# Sheet1.net
KiCad netlist of a schematic drawn in Altium Designer
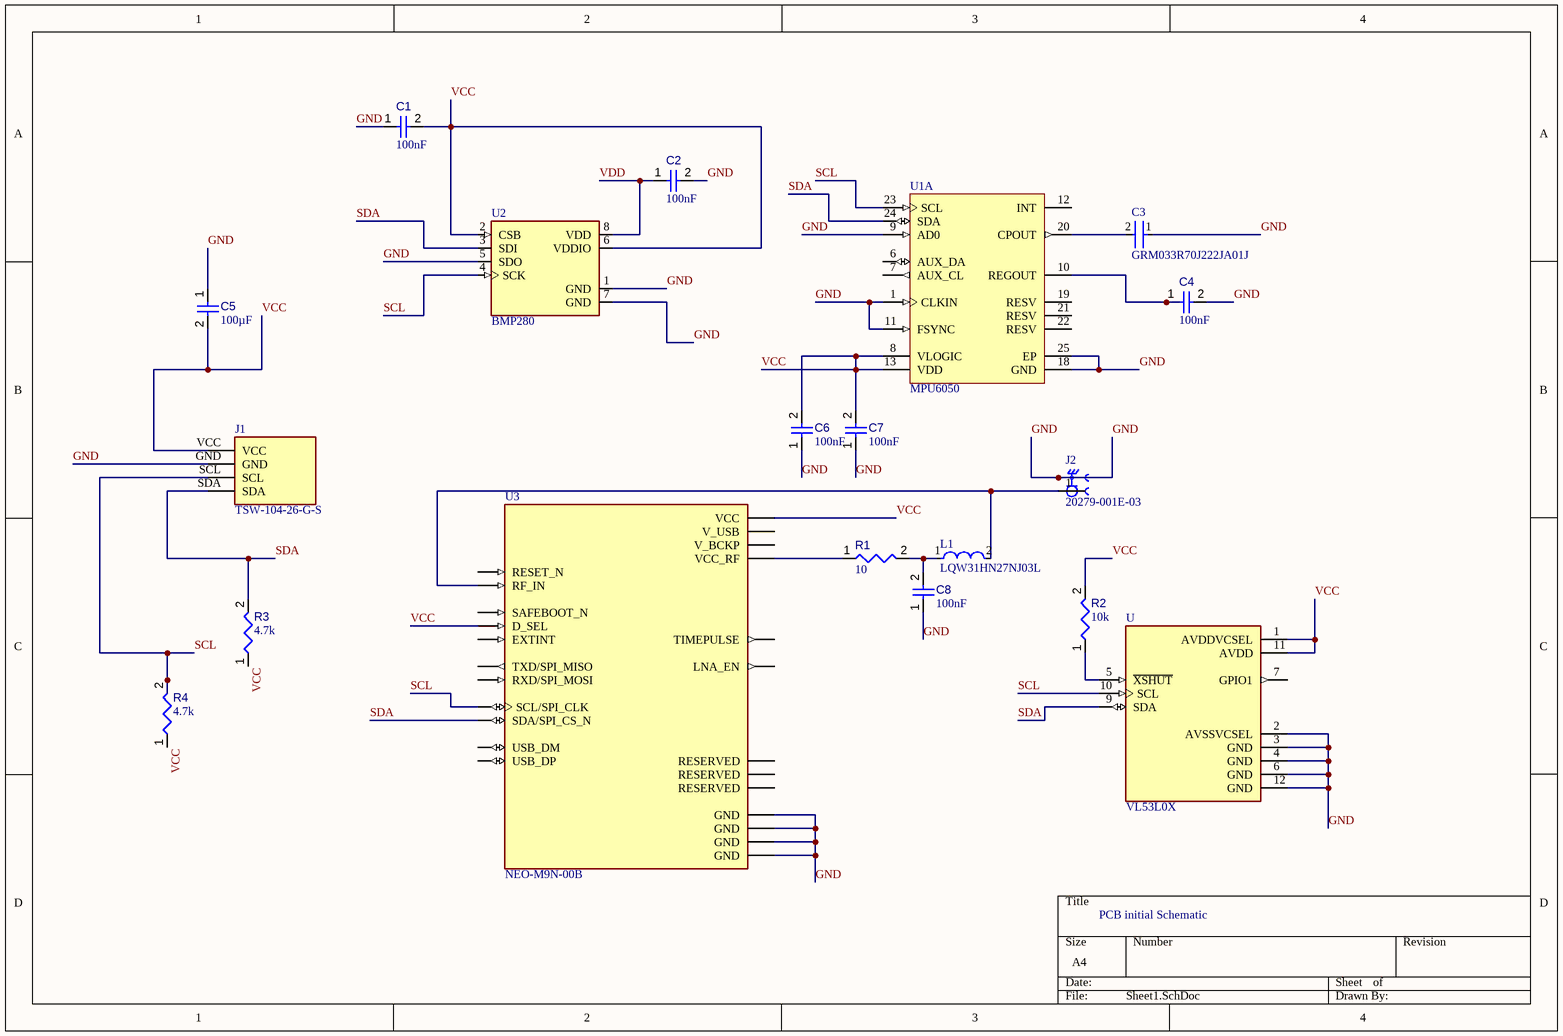
[diagram p0: Sheet1.SchDoc]

(export (version "E")
  (design (tool "Eeschema 10.0.6"))
  (components
    (comp (ref "C1")
      (value "100nF")
      (footprint "CAPC0402(1005)60_L")
      (description "Chip Capacitor, 100nF +/-20%, 10V, 0402, Thickness 0.6 mm")
      (fields (field (name "TOLERANCE") "20%") (field (name "Comment") "Capacitor 100nF +/-20% 10V 0402"))
      (libsource (lib "Lachlan Biersteker") (part "CAP-NP-2"))
    )
    (comp (ref "C2")
      (value "100nF")
      (footprint "CAPC0402(1005)60_L")
      (description "Chip Capacitor, 100nF +/-20%, 10V, 0402, Thickness 0.6 mm")
      (fields (field (name "TOLERANCE") "20%") (field (name "Comment") "Capacitor 100nF +/-20% 10V 0402"))
      (libsource (lib "Lachlan Biersteker") (part "CAP-NP-2"))
    )
    (comp (ref "C3")
      (value "GRM033R70J222JA01J")
      (footprint "FP-GRM033-0_03-IPC_B")
      (description "Chip Multilayer Ceramic Capacitors for General Purpose, 0201, 2200pF, X7R, 15%, 5%, 6.3V")
      (fields (field (name "TOLERANCE") "5%"))
      (libsource (lib "Altium Content Vault") (part "b4654b650e69147ec39a6b967a45e02"))
    )
    (comp (ref "C4")
      (value "100nF")
      (footprint "CAPC1005X56X25LL10T15")
      (description "Chip Capacitor, 0.1 uF, +/- 5%, 16 V, 0402 (1005 Metric)")
      (fields (field (name "TOLERANCE") "5%") (field (name "Comment") "Capacitor 0.1 uF +/- 5% 16 V 0402"))
      (libsource (lib "Lachlan Biersteker") (part "CAP-NP-2"))
    )
    (comp (ref "C5")
      (value "100µF")
      (footprint "CAPC0805(2012)145_L")
      (description "Chip Capacitor, 100µF +/-20%, 6.3V, 0805, Thickness 1.45 mm")
      (fields (field (name "TOLERANCE") "10%") (field (name "Comment") "Capacitor 100µF +/-20% 6.3V 0805"))
      (libsource (lib "Lachlan Biersteker") (part "CAP-NP-2"))
    )
    (comp (ref "C6")
      (value "100nF")
      (footprint "CAPC0402(1005)60_L")
      (description "Chip Capacitor, 100nF +/-20%, 10V, 0402, Thickness 0.6 mm")
      (fields (field (name "TOLERANCE") "20%") (field (name "Comment") "Capacitor 100nF +/-20% 10V 0402"))
      (libsource (lib "Lachlan Biersteker") (part "CAP-NP-2"))
    )
    (comp (ref "C7")
      (value "100nF")
      (footprint "CAPC0402(1005)60_L")
      (description "Chip Capacitor, 100nF +/-20%, 10V, 0402, Thickness 0.6 mm")
      (fields (field (name "TOLERANCE") "20%") (field (name "Comment") "Capacitor 100nF +/-20% 10V 0402"))
      (libsource (lib "Lachlan Biersteker") (part "CAP-NP-2"))
    )
    (comp (ref "C8")
      (value "100nF")
      (footprint "CAPC1608X90X40NL10T20")
      (description "Chip Capacitor, 100 nF, +/- 10%, 50 V, 0603 (1608 Metric)")
      (fields (field (name "TOLERANCE") "10%") (field (name "Comment") "Capacitor 100 nF +/-10% 50 V 0603"))
      (libsource (lib "Lachlan Biersteker") (part "CAP-NP-2"))
    )
    (comp (ref "J1")
      (value "TSW-104-26-G-S")
      (footprint "SAMTEC_TSW-104-26-G-S")
      (libsource (lib "Lachlan Biersteker") (part "TSW-104-26-G-S"))
    )
    (comp (ref "J2")
      (value "20279-001E-03")
      (footprint "IPEX_20279-001E-03")
      (fields (field (name "MF") "I-PEX"))
      (libsource (lib "Lachlan Biersteker") (part "20279-001E-03"))
    )
    (comp (ref "L1")
      (value "LQW31HN27NJ03L")
      (footprint "FP-LQW31HN_03-MFG")
      (description "Wire Wound RF Inductor 27nH ±5% 0.0714Ω 560mA 1206")
      (fields (field (name "TOLERANCE") "5%"))
      (libsource (lib "Altium Content Vault") (part "725321dda6339637d4d059423bc1c3c"))
    )
    (comp (ref "R1")
      (value "10")
      (footprint "RESC0402(1005)_L")
      (description "Chip Resistor, 10 Ohms, +/-1 %, 63 mW, -55 to 155 degC, 0402")
      (fields (field (name "TOLERANCE") "1%") (field (name "POWER") "63mW"))
      (libsource (lib "Lachlan Biersteker") (part "RES-2"))
    )
    (comp (ref "R2")
      (value "10k")
      (footprint "RESC1005X40X25ML05T05")
      (description "Chip Resistor, 10 KOhm, +/- 1%, 0.1 W, -55 to 155 degC, 0402 (1005 Metric)")
      (fields (field (name "TOLERANCE") "1%") (field (name "POWER") "100mW"))
      (libsource (lib "Lachlan Biersteker") (part "RES-2"))
    )
    (comp (ref "R3")
      (value "4.7k")
      (footprint "RESC1005X40X25ML05T05")
      (description "Chip Resistor, 4.7 KOhm, +/- 1%, 0.1 W, -55 to 155 degC, 0402 (1005 Metric)")
      (fields (field (name "POWER") "100mW") (field (name "TOLERANCE") "1%"))
      (libsource (lib "Lachlan Biersteker") (part "RES-2"))
    )
    (comp (ref "R4")
      (value "4.7k")
      (footprint "RESC1005X40X25ML05T05")
      (description "Chip Resistor, 4.7 KOhm, +/- 1%, 0.1 W, -55 to 155 degC, 0402 (1005 Metric)")
      (fields (field (name "POWER") "100mW") (field (name "TOLERANCE") "1%"))
      (libsource (lib "Lachlan Biersteker") (part "RES-2"))
    )
    (comp (ref "U")
      (value "VL53L0X")
      (footprint "SENSOR_VL53L0X")
      (description "VL53L0X - Light, 3D Time-of-Flight _ToF_ Sensor Evaluation Board")
      (fields (field (name "MF") "STMicroelectronics"))
      (libsource (lib "Lachlan Biersteker") (part "VL53L0X"))
    )
    (comp (ref "U1")
      (value "MPU6050")
      (footprint "INSE-QFN-24_V")
      (fields (field (name "MANUFACTURER") "InvenSense"))
      (libsource (lib "Lachlan Biersteker") (part "INSE-MPU6050-QFN-24"))
    )
    (comp (ref "U2")
      (value "BMP280")
      (footprint "XDCR_BMP280")
      (description "BMP280 Absolute Barometric Pressure Sensor for Battery Powered Devices 2 x 2.5mm")
      (libsource (lib "Lachlan Biersteker") (part "BMP280"))
    )
    (comp (ref "U3")
      (value "NEO-M9N-00B")
      (footprint "XCVR_NEO-M9N-00B")
      (description "series RF Receiver BeiDou, Galileo, GLONASS, GNSS, GPS - -167dBm - - Module")
      (fields (field (name "MF") "u-blox"))
      (libsource (lib "Lachlan Biersteker") (part "NEO-M9N-00B"))
    )
  )
  (nets
    (net (code "1") (name "/GND") (class "Default")
      (node (ref "C1") (pin "1") (pinfunction "1_1") (pintype "passive"))
      (node (ref "C2") (pin "2") (pinfunction "2_2") (pintype "passive"))
      (node (ref "C3") (pin "1") (pinfunction "1_1") (pintype "passive"))
      (node (ref "C4") (pin "2") (pinfunction "2_2") (pintype "passive"))
      (node (ref "C5") (pin "1") (pinfunction "1_1") (pintype "passive"))
      (node (ref "C6") (pin "1") (pinfunction "1_1") (pintype "passive"))
      (node (ref "C7") (pin "1") (pinfunction "1_1") (pintype "passive"))
      (node (ref "C8") (pin "1") (pinfunction "1_1") (pintype "passive"))
      (node (ref "J1") (pin "GND") (pinfunction "GND_GND") (pintype "passive"))
      (node (ref "J2") (pin "2") (pinfunction "GROUND_2") (pintype "passive"))
      (node (ref "J2") (pin "3") (pinfunction "GROUND_3") (pintype "passive"))
      (node (ref "U") (pin "12") (pinfunction "GND_12") (pintype "power_in"))
      (node (ref "U") (pin "2") (pinfunction "AVSSVCSEL_2") (pintype "power_in"))
      (node (ref "U") (pin "3") (pinfunction "GND_3") (pintype "power_in"))
      (node (ref "U") (pin "4") (pinfunction "GND_4") (pintype "power_in"))
      (node (ref "U") (pin "6") (pinfunction "GND_6") (pintype "power_in"))
      (node (ref "U1") (pin "1") (pinfunction "CLKIN_1") (pintype "input"))
      (node (ref "U1") (pin "11") (pinfunction "FSYNC_11") (pintype "input"))
      (node (ref "U1") (pin "18") (pinfunction "GND_18") (pintype "power_in"))
      (node (ref "U1") (pin "25") (pinfunction "EP_25") (pintype "passive"))
      (node (ref "U1") (pin "9") (pinfunction "AD0_9") (pintype "input"))
      (node (ref "U2") (pin "1") (pinfunction "GND_1") (pintype "power_in"))
      (node (ref "U2") (pin "5") (pinfunction "SDO_5") (pintype "bidirectional"))
      (node (ref "U2") (pin "7") (pinfunction "GND_7") (pintype "power_in"))
      (node (ref "U3") (pin "10") (pinfunction "GND_10") (pintype "power_in"))
      (node (ref "U3") (pin "12") (pinfunction "GND_12") (pintype "power_in"))
      (node (ref "U3") (pin "13") (pinfunction "GND_13") (pintype "power_in"))
      (node (ref "U3") (pin "24") (pinfunction "GND_24") (pintype "power_in"))
    )
    (net (code "2") (name "/SCL") (class "Default")
      (node (ref "J1") (pin "SCL") (pinfunction "SCL_SCL") (pintype "passive"))
      (node (ref "R4") (pin "2") (pinfunction "2_2") (pintype "passive"))
      (node (ref "U") (pin "10") (pinfunction "SCL_10") (pintype "input"))
      (node (ref "U1") (pin "23") (pinfunction "SCL_23") (pintype "input"))
      (node (ref "U2") (pin "4") (pinfunction "SCK_4") (pintype "input"))
      (node (ref "U3") (pin "19") (pinfunction "SCL/SPI_CLK_19") (pintype "bidirectional"))
    )
    (net (code "3") (name "/SDA") (class "Default")
      (node (ref "J1") (pin "SDA") (pinfunction "SDA_SDA") (pintype "passive"))
      (node (ref "R3") (pin "2") (pinfunction "2_2") (pintype "passive"))
      (node (ref "U") (pin "9") (pinfunction "SDA_9") (pintype "bidirectional"))
      (node (ref "U1") (pin "24") (pinfunction "SDA_24") (pintype "bidirectional"))
      (node (ref "U2") (pin "3") (pinfunction "SDI_3") (pintype "bidirectional"))
      (node (ref "U3") (pin "18") (pinfunction "SDA/SPI_CS_N_18") (pintype "bidirectional"))
    )
    (net (code "4") (name "/VCC") (class "Default")
      (node (ref "C1") (pin "2") (pinfunction "2_2") (pintype "passive"))
      (node (ref "C5") (pin "2") (pinfunction "2_2") (pintype "passive"))
      (node (ref "C6") (pin "2") (pinfunction "2_2") (pintype "passive"))
      (node (ref "C7") (pin "2") (pinfunction "2_2") (pintype "passive"))
      (node (ref "J1") (pin "VCC") (pinfunction "VCC_VCC") (pintype "passive"))
      (node (ref "R2") (pin "2") (pinfunction "2_2") (pintype "passive"))
      (node (ref "R3") (pin "1") (pinfunction "1_1") (pintype "passive"))
      (node (ref "R4") (pin "1") (pinfunction "1_1") (pintype "passive"))
      (node (ref "U") (pin "1") (pinfunction "AVDDVCSEL_1") (pintype "power_in"))
      (node (ref "U") (pin "11") (pinfunction "AVDD_11") (pintype "power_in"))
      (node (ref "U1") (pin "13") (pinfunction "VDD_13") (pintype "power_in"))
      (node (ref "U1") (pin "8") (pinfunction "VLOGIC_8") (pintype "power_in"))
      (node (ref "U2") (pin "2") (pinfunction "CSB_2") (pintype "input"))
      (node (ref "U2") (pin "6") (pinfunction "VDDIO_6") (pintype "power_in"))
      (node (ref "U3") (pin "2") (pinfunction "D_SEL_2") (pintype "input"))
      (node (ref "U3") (pin "23") (pinfunction "VCC_23") (pintype "power_in"))
    )
    (net (code "5") (name "/VDD") (class "Default")
      (node (ref "C2") (pin "1") (pinfunction "1_1") (pintype "passive"))
      (node (ref "U2") (pin "8") (pinfunction "VDD_8") (pintype "power_in"))
    )
    (net (code "6") (name "Net-(C8-Pad2)") (class "Default")
      (node (ref "C8") (pin "2") (pinfunction "2_2") (pintype "passive"))
      (node (ref "L1") (pin "1") (pinfunction "1_1") (pintype "passive"))
      (node (ref "R1") (pin "2") (pinfunction "2_2") (pintype "passive"))
    )
    (net (code "7") (name "Net-(J2-SIGNAL)") (class "Default")
      (node (ref "J2") (pin "1") (pinfunction "SIGNAL_1") (pintype "passive"))
      (node (ref "L1") (pin "2") (pinfunction "2_2") (pintype "passive"))
      (node (ref "U3") (pin "11") (pinfunction "RF_IN_11") (pintype "input"))
    )
    (net (code "8") (name "Net-(U-~{XSHUT})") (class "Default")
      (node (ref "R2") (pin "1") (pinfunction "1_1") (pintype "passive"))
      (node (ref "U") (pin "5") (pinfunction "~{XSHUT}_5") (pintype "input"))
    )
    (net (code "9") (name "Net-(U1A-CPOUT)") (class "Default")
      (node (ref "C3") (pin "2") (pinfunction "2_2") (pintype "passive"))
      (node (ref "U1") (pin "20") (pinfunction "CPOUT_20") (pintype "output"))
    )
    (net (code "10") (name "Net-(U1A-REGOUT)") (class "Default")
      (node (ref "C4") (pin "1") (pinfunction "1_1") (pintype "passive"))
      (node (ref "U1") (pin "10") (pinfunction "REGOUT_10") (pintype "passive"))
    )
    (net (code "11") (name "Net-(U3-VCC_RF)") (class "Default")
      (node (ref "R1") (pin "1") (pinfunction "1_1") (pintype "passive"))
      (node (ref "U3") (pin "9") (pinfunction "VCC_RF_9") (pintype "power_in"))
    )
    (net (code "12") (name "unconnected-(U-GPIO1-Pad7)") (class "Default")
      (node (ref "U") (pin "7") (pinfunction "GPIO1_7") (pintype "output"))
    )
    (net (code "13") (name "unconnected-(U1A-AUX_CL-Pad7)") (class "Default")
      (node (ref "U1") (pin "7") (pinfunction "AUX_CL_7") (pintype "output"))
    )
    (net (code "14") (name "unconnected-(U1A-AUX_DA-Pad6)") (class "Default")
      (node (ref "U1") (pin "6") (pinfunction "AUX_DA_6") (pintype "bidirectional"))
    )
    (net (code "15") (name "unconnected-(U1A-INT-Pad12)") (class "Default")
      (node (ref "U1") (pin "12") (pinfunction "INT_12") (pintype "open_collector"))
    )
    (net (code "16") (name "unconnected-(U1A-RESV-Pad19)") (class "Default")
      (node (ref "U1") (pin "19") (pinfunction "RESV_19") (pintype "passive"))
    )
    (net (code "17") (name "unconnected-(U1A-RESV-Pad21)") (class "Default")
      (node (ref "U1") (pin "21") (pinfunction "RESV_21") (pintype "passive"))
    )
    (net (code "18") (name "unconnected-(U1A-RESV-Pad22)") (class "Default")
      (node (ref "U1") (pin "22") (pinfunction "RESV_22") (pintype "passive"))
    )
    (net (code "19") (name "unconnected-(U3-EXTINT-Pad4)") (class "Default")
      (node (ref "U3") (pin "4") (pinfunction "EXTINT_4") (pintype "input"))
    )
    (net (code "20") (name "unconnected-(U3-LNA_EN-Pad14)") (class "Default")
      (node (ref "U3") (pin "14") (pinfunction "LNA_EN_14") (pintype "output"))
    )
    (net (code "21") (name "unconnected-(U3-RESERVED-Pad15)") (class "Default")
      (node (ref "U3") (pin "15") (pinfunction "RESERVED_15") (pintype "passive"))
    )
    (net (code "22") (name "unconnected-(U3-RESERVED-Pad16)") (class "Default")
      (node (ref "U3") (pin "16") (pinfunction "RESERVED_16") (pintype "passive"))
    )
    (net (code "23") (name "unconnected-(U3-RESERVED-Pad17)") (class "Default")
      (node (ref "U3") (pin "17") (pinfunction "RESERVED_17") (pintype "passive"))
    )
    (net (code "24") (name "unconnected-(U3-RESET_N-Pad8)") (class "Default")
      (node (ref "U3") (pin "8") (pinfunction "RESET_N_8") (pintype "input"))
    )
    (net (code "25") (name "unconnected-(U3-RXD{slash}SPI_MOSI-Pad21)") (class "Default")
      (node (ref "U3") (pin "21") (pinfunction "RXD/SPI_MOSI_21") (pintype "input"))
    )
    (net (code "26") (name "unconnected-(U3-SAFEBOOT_N-Pad1)") (class "Default")
      (node (ref "U3") (pin "1") (pinfunction "SAFEBOOT_N_1") (pintype "input"))
    )
    (net (code "27") (name "unconnected-(U3-TIMEPULSE-Pad3)") (class "Default")
      (node (ref "U3") (pin "3") (pinfunction "TIMEPULSE_3") (pintype "output"))
    )
    (net (code "28") (name "unconnected-(U3-TXD{slash}SPI_MISO-Pad20)") (class "Default")
      (node (ref "U3") (pin "20") (pinfunction "TXD/SPI_MISO_20") (pintype "output"))
    )
    (net (code "29") (name "unconnected-(U3-USB_DM-Pad5)") (class "Default")
      (node (ref "U3") (pin "5") (pinfunction "USB_DM_5") (pintype "bidirectional"))
    )
    (net (code "30") (name "unconnected-(U3-USB_DP-Pad6)") (class "Default")
      (node (ref "U3") (pin "6") (pinfunction "USB_DP_6") (pintype "bidirectional"))
    )
    (net (code "31") (name "unconnected-(U3-V_BCKP-Pad22)") (class "Default")
      (node (ref "U3") (pin "22") (pinfunction "V_BCKP_22") (pintype "power_in"))
    )
    (net (code "32") (name "unconnected-(U3-V_USB-Pad7)") (class "Default")
      (node (ref "U3") (pin "7") (pinfunction "V_USB_7") (pintype "power_in"))
    )
  )
)
